# TCS32X0.net
KiCad netlist of a schematic drawn in EAGLE
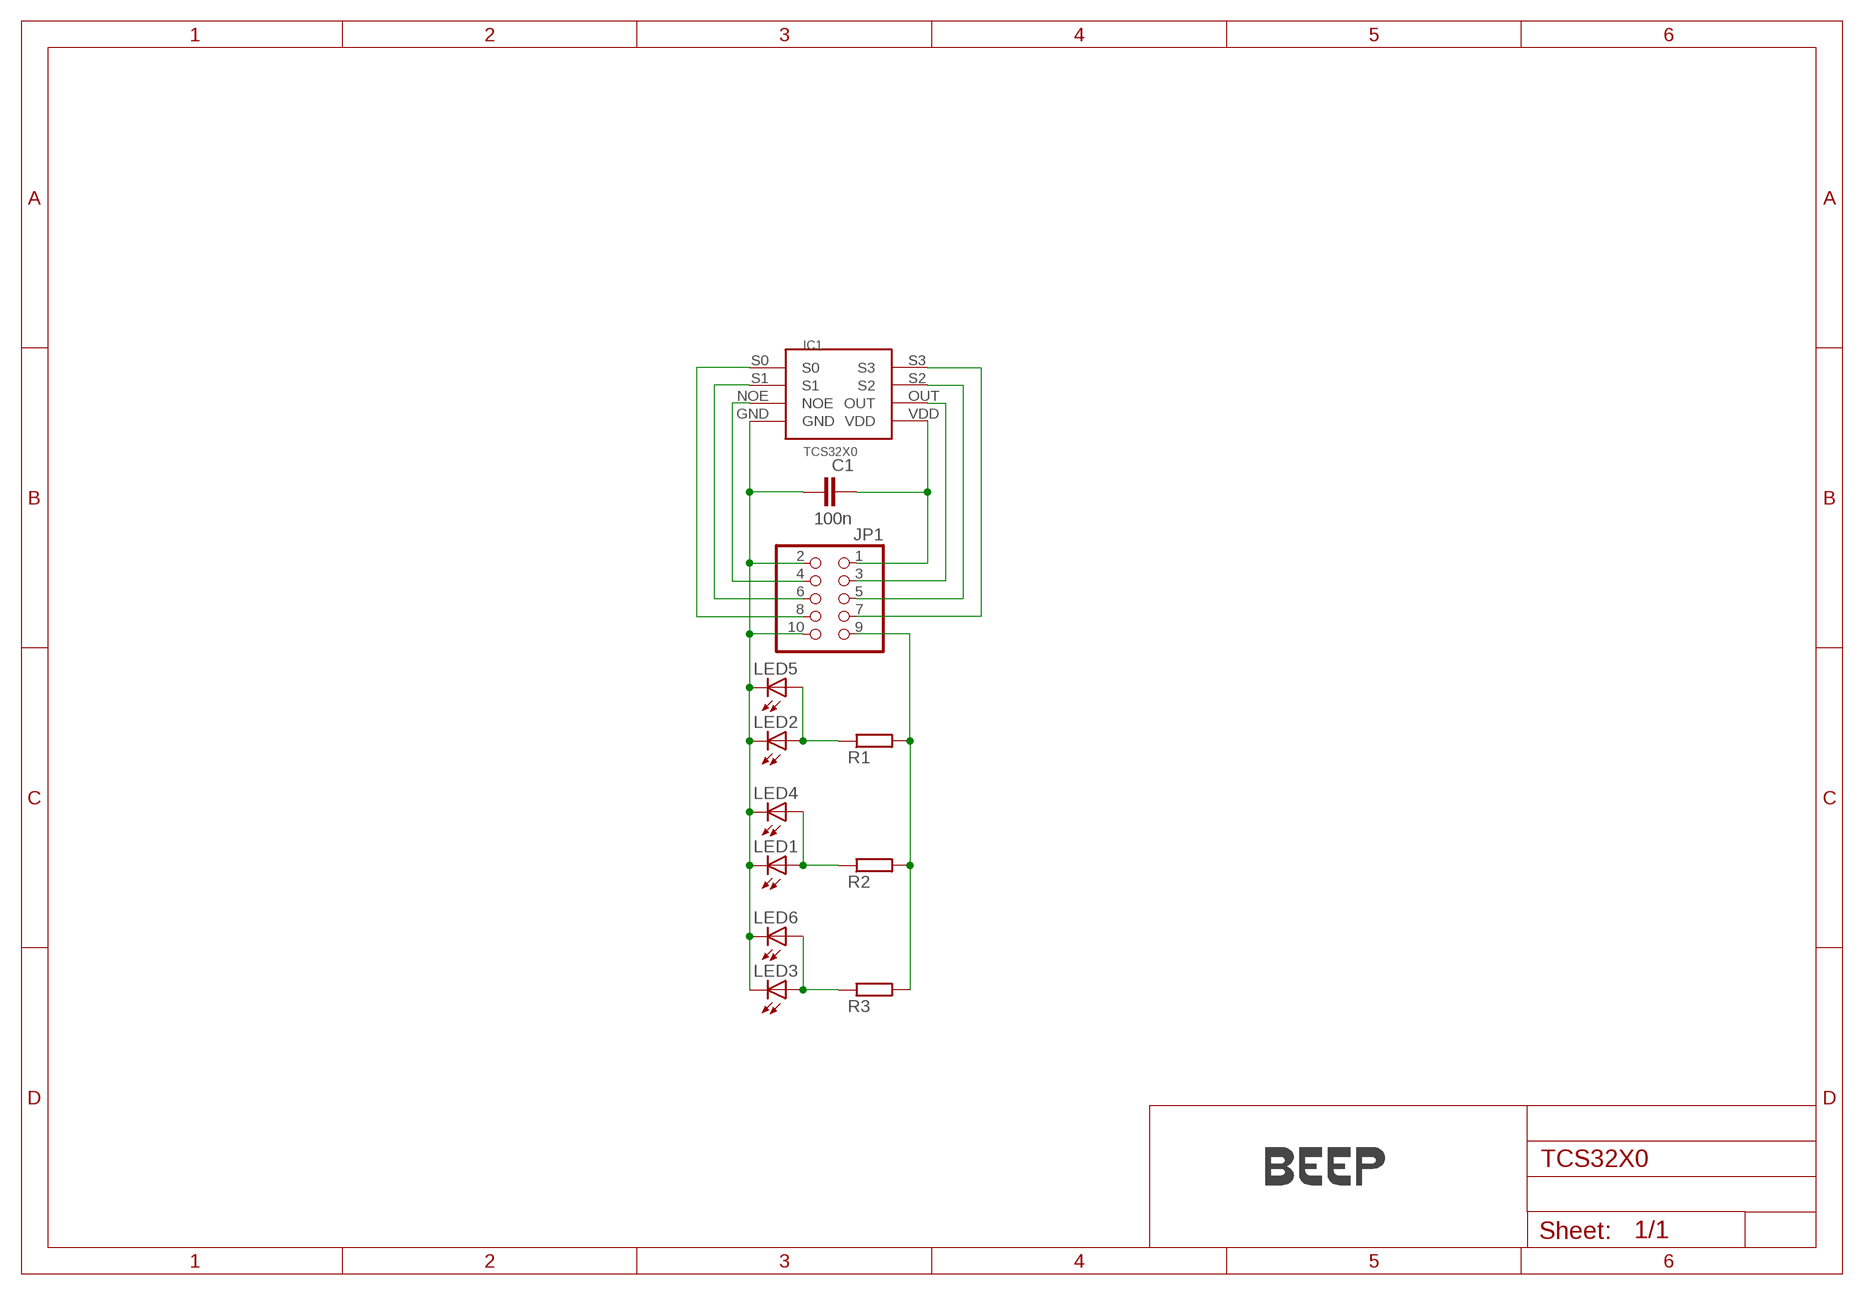
[diagram p0: schematic, sheet 1]

(export (version "E")
  (design (tool "Eeschema 10.0.6"))
  (components
    (comp (ref "C1")
      (value "100n")
      (footprint "eagle-import:C0805")
      (libsource (lib "eagle-import") (part "C-EUC0805"))
    )
    (comp (ref "IC1")
      (value "TCS32X0")
      (footprint "eagle-import:TCS32X0")
      (libsource (lib "eagle-import") (part "TCS32X0"))
    )
    (comp (ref "JP1")
      (value "PINHD-2X5")
      (footprint "eagle-import:2X05")
      (libsource (lib "eagle-import") (part "PINHD-2X5"))
    )
    (comp (ref "LED1")
      (value "LED3MM")
      (footprint "eagle-import:LED3MM")
      (libsource (lib "eagle-import") (part "LED3MM"))
    )
    (comp (ref "LED2")
      (value "LED3MM")
      (footprint "eagle-import:LED3MM")
      (libsource (lib "eagle-import") (part "LED3MM"))
    )
    (comp (ref "LED3")
      (value "LED3MM")
      (footprint "eagle-import:LED3MM")
      (libsource (lib "eagle-import") (part "LED3MM"))
    )
    (comp (ref "LED4")
      (value "NFSG036BT")
      (footprint "eagle-import:NFSG036BT")
      (libsource (lib "eagle-import") (part "NFSG036BT"))
    )
    (comp (ref "LED5")
      (value "NFSG036BT")
      (footprint "eagle-import:NFSG036BT")
      (libsource (lib "eagle-import") (part "NFSG036BT"))
    )
    (comp (ref "LED6")
      (value "NFSG036BT")
      (footprint "eagle-import:NFSG036BT")
      (libsource (lib "eagle-import") (part "NFSG036BT"))
    )
    (comp (ref "R1")
      (value "R-EU_M0805")
      (footprint "eagle-import:M0805")
      (libsource (lib "eagle-import") (part "R-EU_M0805"))
    )
    (comp (ref "R2")
      (value "R-EU_M0805")
      (footprint "eagle-import:M0805")
      (libsource (lib "eagle-import") (part "R-EU_M0805"))
    )
    (comp (ref "R3")
      (value "R-EU_M0805")
      (footprint "eagle-import:M0805")
      (libsource (lib "eagle-import") (part "R-EU_M0805"))
    )
    (comp (ref "U$1")
      (value "LOGO-COPPER4")
      (footprint "eagle-import:COPPER4")
      (libsource (lib "eagle-import") (part "LOGO-COPPER4"))
    )
  )
  (nets
    (net (code "1") (name "Net-(C1-Pad2)") (class "Default")
      (node (ref "C1") (pin "2") (pinfunction "2_2") (pintype "passive"))
      (node (ref "IC1") (pin "VDD") (pinfunction "VDD_VDD") (pintype "power_in"))
      (node (ref "JP1") (pin "1") (pinfunction "1_1") (pintype "passive"))
    )
    (net (code "2") (name "Net-(IC1-PadNOE)") (class "Default")
      (node (ref "IC1") (pin "NOE") (pinfunction "NOE_NOE") (pintype "output"))
      (node (ref "JP1") (pin "4") (pinfunction "4_4") (pintype "passive"))
    )
    (net (code "3") (name "Net-(IC1-PadOUT)") (class "Default")
      (node (ref "IC1") (pin "OUT") (pinfunction "OUT_OUT") (pintype "output"))
      (node (ref "JP1") (pin "3") (pinfunction "3_3") (pintype "passive"))
    )
    (net (code "4") (name "Net-(IC1-PadS0)") (class "Default")
      (node (ref "IC1") (pin "S0") (pinfunction "S0_S0") (pintype "input"))
      (node (ref "JP1") (pin "8") (pinfunction "8_8") (pintype "passive"))
    )
    (net (code "5") (name "Net-(IC1-PadS1)") (class "Default")
      (node (ref "IC1") (pin "S1") (pinfunction "S1_S1") (pintype "input"))
      (node (ref "JP1") (pin "6") (pinfunction "6_6") (pintype "passive"))
    )
    (net (code "6") (name "Net-(IC1-PadS2)") (class "Default")
      (node (ref "IC1") (pin "S2") (pinfunction "S2_S2") (pintype "input"))
      (node (ref "JP1") (pin "5") (pinfunction "5_5") (pintype "passive"))
    )
    (net (code "7") (name "Net-(IC1-PadS3)") (class "Default")
      (node (ref "IC1") (pin "S3") (pinfunction "S3_S3") (pintype "input"))
      (node (ref "JP1") (pin "7") (pinfunction "7_7") (pintype "passive"))
    )
    (net (code "8") (name "Net-(JP1-Pad9)") (class "Default")
      (node (ref "JP1") (pin "9") (pinfunction "9_9") (pintype "passive"))
      (node (ref "R1") (pin "2") (pinfunction "2_2") (pintype "passive"))
      (node (ref "R2") (pin "2") (pinfunction "2_2") (pintype "passive"))
      (node (ref "R3") (pin "2") (pinfunction "2_2") (pintype "passive"))
    )
    (net (code "9") (name "Net-(LED1-C)") (class "Default")
      (node (ref "C1") (pin "1") (pinfunction "1_1") (pintype "passive"))
      (node (ref "IC1") (pin "GND") (pinfunction "GND_GND") (pintype "power_in"))
      (node (ref "JP1") (pin "10") (pinfunction "10_10") (pintype "passive"))
      (node (ref "JP1") (pin "2") (pinfunction "2_2") (pintype "passive"))
      (node (ref "LED1") (pin "K") (pinfunction "C_K") (pintype "passive"))
      (node (ref "LED2") (pin "K") (pinfunction "C_K") (pintype "passive"))
      (node (ref "LED3") (pin "K") (pinfunction "C_K") (pintype "passive"))
      (node (ref "LED4") (pin "C") (pinfunction "C_C") (pintype "passive"))
      (node (ref "LED5") (pin "C") (pinfunction "C_C") (pintype "passive"))
      (node (ref "LED6") (pin "C") (pinfunction "C_C") (pintype "passive"))
    )
    (net (code "10") (name "Net-(LED1-PadA)") (class "Default")
      (node (ref "LED1") (pin "A") (pinfunction "A_A") (pintype "passive"))
      (node (ref "LED4") (pin "A") (pinfunction "A_A") (pintype "passive"))
      (node (ref "R2") (pin "1") (pinfunction "1_1") (pintype "passive"))
    )
    (net (code "11") (name "Net-(LED2-PadA)") (class "Default")
      (node (ref "LED2") (pin "A") (pinfunction "A_A") (pintype "passive"))
      (node (ref "LED5") (pin "A") (pinfunction "A_A") (pintype "passive"))
      (node (ref "R1") (pin "1") (pinfunction "1_1") (pintype "passive"))
    )
    (net (code "12") (name "Net-(LED3-PadA)") (class "Default")
      (node (ref "LED3") (pin "A") (pinfunction "A_A") (pintype "passive"))
      (node (ref "LED6") (pin "A") (pinfunction "A_A") (pintype "passive"))
      (node (ref "R3") (pin "1") (pinfunction "1_1") (pintype "passive"))
    )
  )
)
